# 06_MOV16_SourceRegister.net
KiCad netlist of a schematic drawn in EAGLE
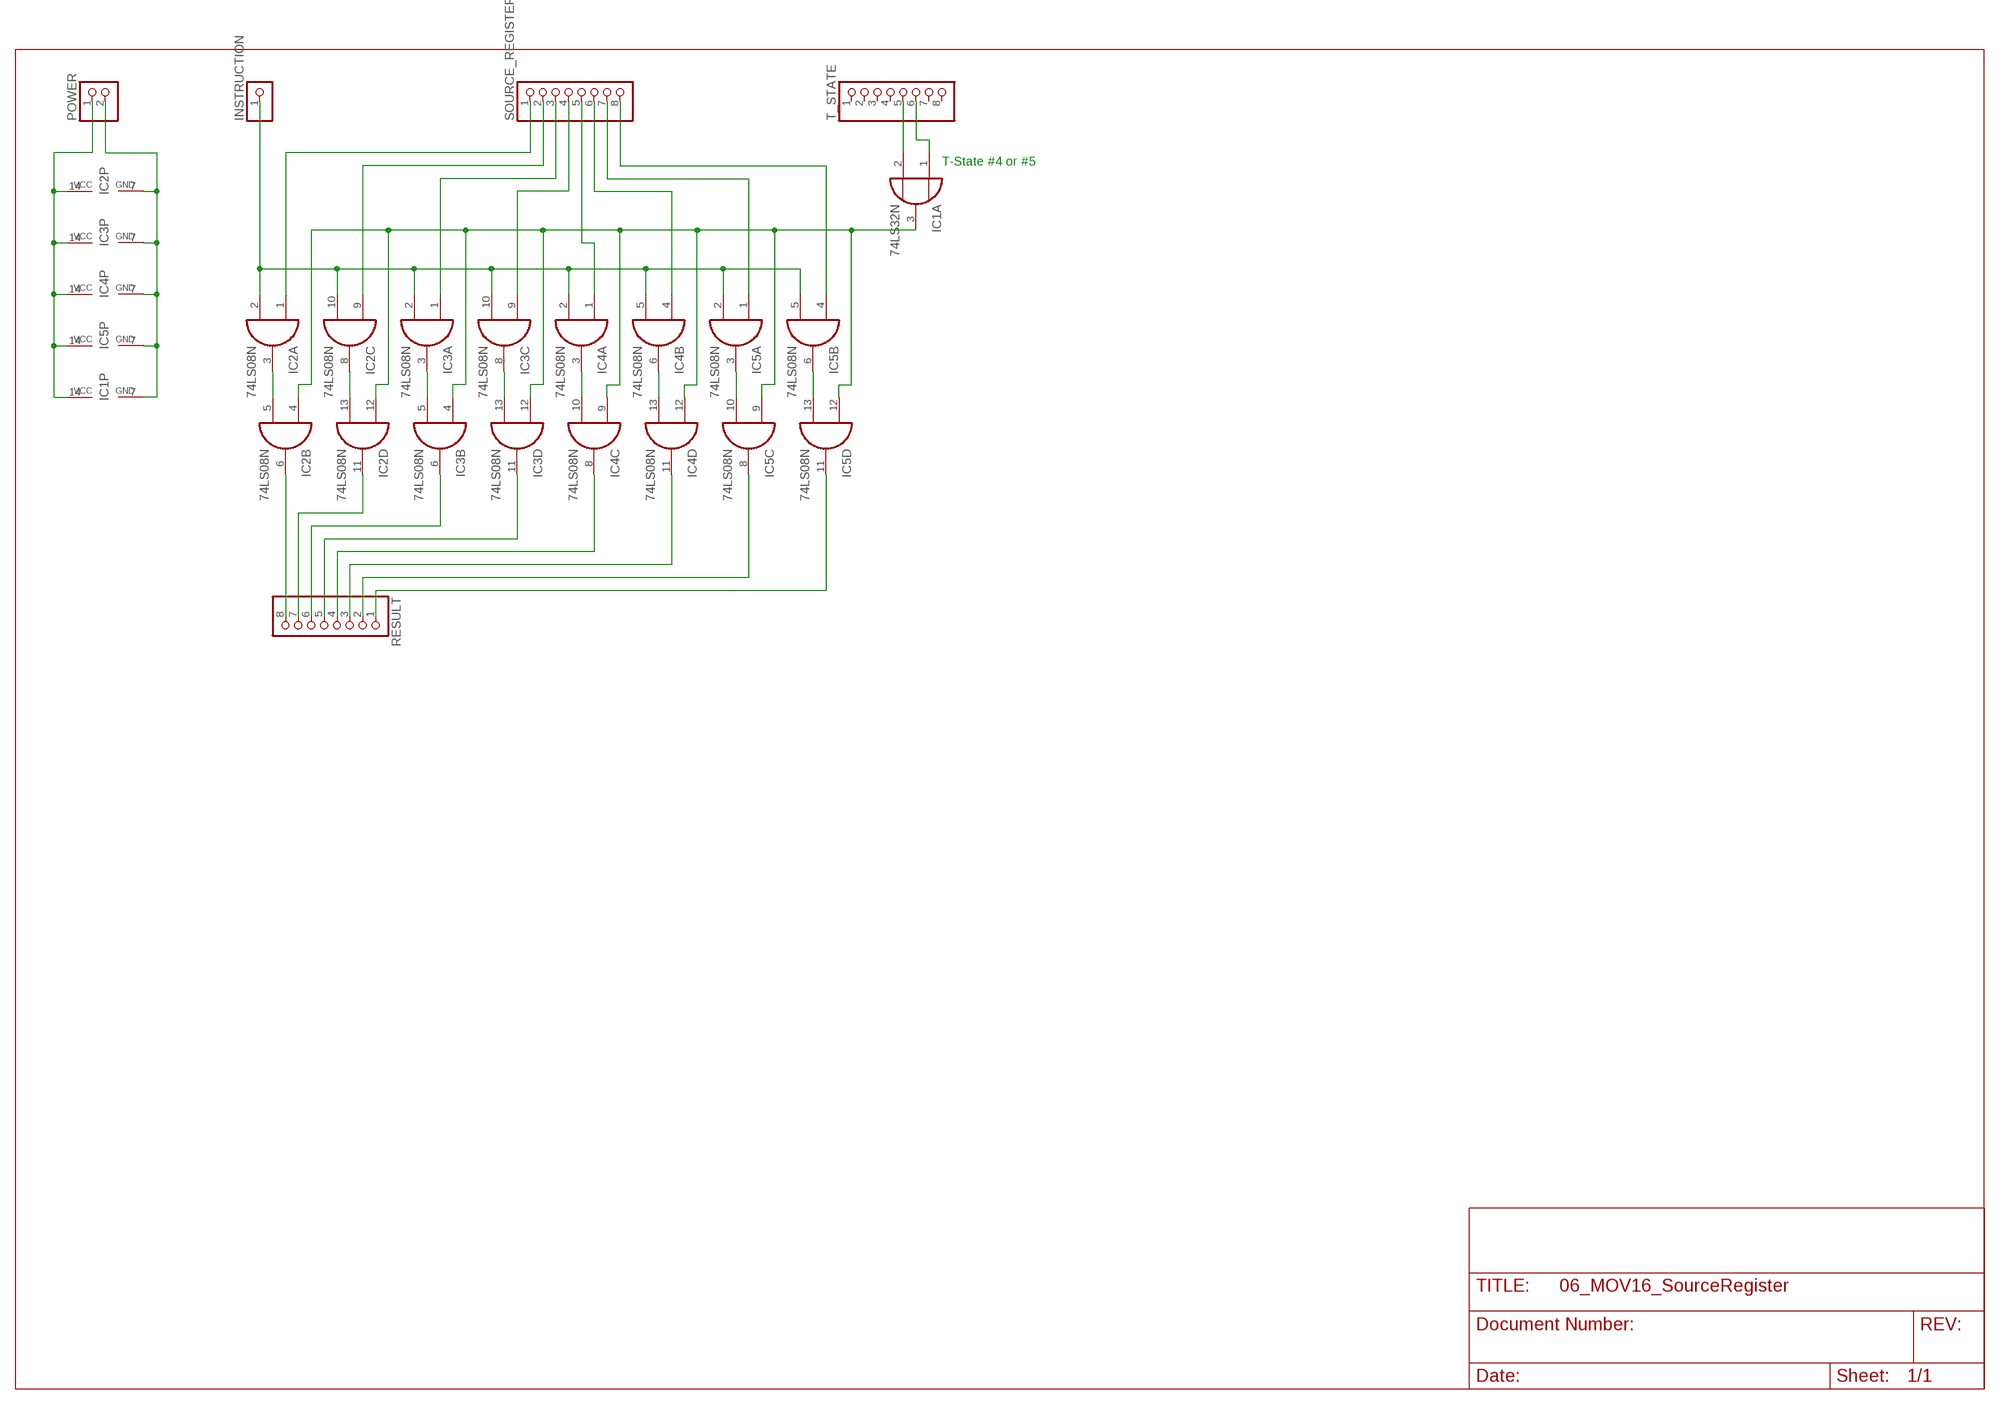
[diagram p0: schematic, sheet 1]

(export (version "E")
  (design (tool "Eeschema 10.0.6"))
  (components
    (comp (ref "IC1")
      (value "74LS32N")
      (footprint "eagle-import:DIL14")
      (libsource (lib "eagle-import") (part "7432NLS"))
    )
    (comp (ref "IC2")
      (value "74LS08N")
      (footprint "eagle-import:DIL14")
      (libsource (lib "eagle-import") (part "7408NLS"))
    )
    (comp (ref "IC3")
      (value "74LS08N")
      (footprint "eagle-import:DIL14")
      (libsource (lib "eagle-import") (part "7408NLS"))
    )
    (comp (ref "IC4")
      (value "74LS08N")
      (footprint "eagle-import:DIL14")
      (libsource (lib "eagle-import") (part "7408NLS"))
    )
    (comp (ref "IC5")
      (value "74LS08N")
      (footprint "eagle-import:DIL14")
      (libsource (lib "eagle-import") (part "7408NLS"))
    )
    (comp (ref "INSTRUCTION")
      (value "PINHD-1X1")
      (footprint "eagle-import:1X01")
      (libsource (lib "eagle-import") (part "PINHD-1X1"))
    )
    (comp (ref "POWER")
      (value "PINHD-1X2")
      (footprint "eagle-import:1X02")
      (libsource (lib "eagle-import") (part "PINHD-1X2"))
    )
    (comp (ref "RESULT")
      (value "PINHD-1X8")
      (footprint "eagle-import:1X08")
      (libsource (lib "eagle-import") (part "PINHD-1X8"))
    )
    (comp (ref "SOURCE_REGISTER")
      (value "PINHD-1X8")
      (footprint "eagle-import:1X08")
      (libsource (lib "eagle-import") (part "PINHD-1X8"))
    )
    (comp (ref "T_STATE")
      (value "PINHD-1X8")
      (footprint "eagle-import:1X08")
      (libsource (lib "eagle-import") (part "PINHD-1X8"))
    )
  )
  (nets
    (net (code "1") (name "Net-(IC1A-I0)") (class "Default")
      (node (ref "IC1") (pin "1") (pinfunction "I0_1") (pintype "input"))
      (node (ref "T_STATE") (pin "6") (pinfunction "6_6") (pintype "passive"))
    )
    (net (code "2") (name "Net-(IC1A-I1)") (class "Default")
      (node (ref "IC1") (pin "2") (pinfunction "I1_2") (pintype "input"))
      (node (ref "T_STATE") (pin "5") (pinfunction "5_5") (pintype "passive"))
    )
    (net (code "3") (name "Net-(IC1A-O)") (class "Default")
      (node (ref "IC1") (pin "3") (pinfunction "O_3") (pintype "output"))
      (node (ref "IC2") (pin "12") (pinfunction "I0_12") (pintype "input"))
      (node (ref "IC2") (pin "4") (pinfunction "I0_4") (pintype "input"))
      (node (ref "IC3") (pin "12") (pinfunction "I0_12") (pintype "input"))
      (node (ref "IC3") (pin "4") (pinfunction "I0_4") (pintype "input"))
      (node (ref "IC4") (pin "12") (pinfunction "I0_12") (pintype "input"))
      (node (ref "IC4") (pin "9") (pinfunction "I0_9") (pintype "input"))
      (node (ref "IC5") (pin "12") (pinfunction "I0_12") (pintype "input"))
      (node (ref "IC5") (pin "9") (pinfunction "I0_9") (pintype "input"))
    )
    (net (code "4") (name "Net-(IC1E-GND)") (class "Default")
      (node (ref "IC1") (pin "7") (pinfunction "GND_7") (pintype "power_in"))
      (node (ref "IC2") (pin "7") (pinfunction "GND_7") (pintype "power_in"))
      (node (ref "IC3") (pin "7") (pinfunction "GND_7") (pintype "power_in"))
      (node (ref "IC4") (pin "7") (pinfunction "GND_7") (pintype "power_in"))
      (node (ref "IC5") (pin "7") (pinfunction "GND_7") (pintype "power_in"))
      (node (ref "POWER") (pin "2") (pinfunction "2_2") (pintype "passive"))
    )
    (net (code "5") (name "Net-(IC1E-VCC)") (class "Default")
      (node (ref "IC1") (pin "14") (pinfunction "VCC_14") (pintype "power_in"))
      (node (ref "IC2") (pin "14") (pinfunction "VCC_14") (pintype "power_in"))
      (node (ref "IC3") (pin "14") (pinfunction "VCC_14") (pintype "power_in"))
      (node (ref "IC4") (pin "14") (pinfunction "VCC_14") (pintype "power_in"))
      (node (ref "IC5") (pin "14") (pinfunction "VCC_14") (pintype "power_in"))
      (node (ref "POWER") (pin "1") (pinfunction "1_1") (pintype "passive"))
    )
    (net (code "6") (name "Net-(IC2A-I0)") (class "Default")
      (node (ref "IC2") (pin "1") (pinfunction "I0_1") (pintype "input"))
      (node (ref "SOURCE_REGISTER") (pin "1") (pinfunction "1_1") (pintype "passive"))
    )
    (net (code "7") (name "Net-(IC2A-I1)") (class "Default")
      (node (ref "IC2") (pin "10") (pinfunction "I1_10") (pintype "input"))
      (node (ref "IC2") (pin "2") (pinfunction "I1_2") (pintype "input"))
      (node (ref "IC3") (pin "10") (pinfunction "I1_10") (pintype "input"))
      (node (ref "IC3") (pin "2") (pinfunction "I1_2") (pintype "input"))
      (node (ref "IC4") (pin "2") (pinfunction "I1_2") (pintype "input"))
      (node (ref "IC4") (pin "5") (pinfunction "I1_5") (pintype "input"))
      (node (ref "IC5") (pin "2") (pinfunction "I1_2") (pintype "input"))
      (node (ref "IC5") (pin "5") (pinfunction "I1_5") (pintype "input"))
      (node (ref "INSTRUCTION") (pin "1") (pinfunction "1_1") (pintype "passive"))
    )
    (net (code "8") (name "Net-(IC2A-O)") (class "Default")
      (node (ref "IC2") (pin "3") (pinfunction "O_3") (pintype "output"))
      (node (ref "IC2") (pin "5") (pinfunction "I1_5") (pintype "input"))
    )
    (net (code "9") (name "Net-(IC2B-O)") (class "Default")
      (node (ref "IC2") (pin "6") (pinfunction "O_6") (pintype "output"))
      (node (ref "RESULT") (pin "8") (pinfunction "8_8") (pintype "passive"))
    )
    (net (code "10") (name "Net-(IC2C-I0)") (class "Default")
      (node (ref "IC2") (pin "9") (pinfunction "I0_9") (pintype "input"))
      (node (ref "SOURCE_REGISTER") (pin "2") (pinfunction "2_2") (pintype "passive"))
    )
    (net (code "11") (name "Net-(IC2C-O)") (class "Default")
      (node (ref "IC2") (pin "13") (pinfunction "I1_13") (pintype "input"))
      (node (ref "IC2") (pin "8") (pinfunction "O_8") (pintype "output"))
    )
    (net (code "12") (name "Net-(IC2D-O)") (class "Default")
      (node (ref "IC2") (pin "11") (pinfunction "O_11") (pintype "output"))
      (node (ref "RESULT") (pin "7") (pinfunction "7_7") (pintype "passive"))
    )
    (net (code "13") (name "Net-(IC3A-I0)") (class "Default")
      (node (ref "IC3") (pin "1") (pinfunction "I0_1") (pintype "input"))
      (node (ref "SOURCE_REGISTER") (pin "3") (pinfunction "3_3") (pintype "passive"))
    )
    (net (code "14") (name "Net-(IC3A-O)") (class "Default")
      (node (ref "IC3") (pin "3") (pinfunction "O_3") (pintype "output"))
      (node (ref "IC3") (pin "5") (pinfunction "I1_5") (pintype "input"))
    )
    (net (code "15") (name "Net-(IC3B-O)") (class "Default")
      (node (ref "IC3") (pin "6") (pinfunction "O_6") (pintype "output"))
      (node (ref "RESULT") (pin "6") (pinfunction "6_6") (pintype "passive"))
    )
    (net (code "16") (name "Net-(IC3C-I0)") (class "Default")
      (node (ref "IC3") (pin "9") (pinfunction "I0_9") (pintype "input"))
      (node (ref "SOURCE_REGISTER") (pin "4") (pinfunction "4_4") (pintype "passive"))
    )
    (net (code "17") (name "Net-(IC3C-O)") (class "Default")
      (node (ref "IC3") (pin "13") (pinfunction "I1_13") (pintype "input"))
      (node (ref "IC3") (pin "8") (pinfunction "O_8") (pintype "output"))
    )
    (net (code "18") (name "Net-(IC3D-O)") (class "Default")
      (node (ref "IC3") (pin "11") (pinfunction "O_11") (pintype "output"))
      (node (ref "RESULT") (pin "5") (pinfunction "5_5") (pintype "passive"))
    )
    (net (code "19") (name "Net-(IC4A-I0)") (class "Default")
      (node (ref "IC4") (pin "1") (pinfunction "I0_1") (pintype "input"))
      (node (ref "SOURCE_REGISTER") (pin "5") (pinfunction "5_5") (pintype "passive"))
    )
    (net (code "20") (name "Net-(IC4A-O)") (class "Default")
      (node (ref "IC4") (pin "10") (pinfunction "I1_10") (pintype "input"))
      (node (ref "IC4") (pin "3") (pinfunction "O_3") (pintype "output"))
    )
    (net (code "21") (name "Net-(IC4B-I0)") (class "Default")
      (node (ref "IC4") (pin "4") (pinfunction "I0_4") (pintype "input"))
      (node (ref "SOURCE_REGISTER") (pin "6") (pinfunction "6_6") (pintype "passive"))
    )
    (net (code "22") (name "Net-(IC4B-O)") (class "Default")
      (node (ref "IC4") (pin "13") (pinfunction "I1_13") (pintype "input"))
      (node (ref "IC4") (pin "6") (pinfunction "O_6") (pintype "output"))
    )
    (net (code "23") (name "Net-(IC4C-O)") (class "Default")
      (node (ref "IC4") (pin "8") (pinfunction "O_8") (pintype "output"))
      (node (ref "RESULT") (pin "4") (pinfunction "4_4") (pintype "passive"))
    )
    (net (code "24") (name "Net-(IC4D-O)") (class "Default")
      (node (ref "IC4") (pin "11") (pinfunction "O_11") (pintype "output"))
      (node (ref "RESULT") (pin "3") (pinfunction "3_3") (pintype "passive"))
    )
    (net (code "25") (name "Net-(IC5A-I0)") (class "Default")
      (node (ref "IC5") (pin "1") (pinfunction "I0_1") (pintype "input"))
      (node (ref "SOURCE_REGISTER") (pin "7") (pinfunction "7_7") (pintype "passive"))
    )
    (net (code "26") (name "Net-(IC5A-O)") (class "Default")
      (node (ref "IC5") (pin "10") (pinfunction "I1_10") (pintype "input"))
      (node (ref "IC5") (pin "3") (pinfunction "O_3") (pintype "output"))
    )
    (net (code "27") (name "Net-(IC5B-I0)") (class "Default")
      (node (ref "IC5") (pin "4") (pinfunction "I0_4") (pintype "input"))
      (node (ref "SOURCE_REGISTER") (pin "8") (pinfunction "8_8") (pintype "passive"))
    )
    (net (code "28") (name "Net-(IC5B-O)") (class "Default")
      (node (ref "IC5") (pin "13") (pinfunction "I1_13") (pintype "input"))
      (node (ref "IC5") (pin "6") (pinfunction "O_6") (pintype "output"))
    )
    (net (code "29") (name "Net-(IC5C-O)") (class "Default")
      (node (ref "IC5") (pin "8") (pinfunction "O_8") (pintype "output"))
      (node (ref "RESULT") (pin "2") (pinfunction "2_2") (pintype "passive"))
    )
    (net (code "30") (name "Net-(IC5D-O)") (class "Default")
      (node (ref "IC5") (pin "11") (pinfunction "O_11") (pintype "output"))
      (node (ref "RESULT") (pin "1") (pinfunction "1_1") (pintype "passive"))
    )
    (net (code "31") (name "unconnected-(T_STATE-Pad1)") (class "Default")
      (node (ref "T_STATE") (pin "1") (pinfunction "1_1") (pintype "passive"))
    )
    (net (code "32") (name "unconnected-(T_STATE-Pad2)") (class "Default")
      (node (ref "T_STATE") (pin "2") (pinfunction "2_2") (pintype "passive"))
    )
    (net (code "33") (name "unconnected-(T_STATE-Pad3)") (class "Default")
      (node (ref "T_STATE") (pin "3") (pinfunction "3_3") (pintype "passive"))
    )
    (net (code "34") (name "unconnected-(T_STATE-Pad4)") (class "Default")
      (node (ref "T_STATE") (pin "4") (pinfunction "4_4") (pintype "passive"))
    )
    (net (code "35") (name "unconnected-(T_STATE-Pad7)") (class "Default")
      (node (ref "T_STATE") (pin "7") (pinfunction "7_7") (pintype "passive"))
    )
    (net (code "36") (name "unconnected-(T_STATE-Pad8)") (class "Default")
      (node (ref "T_STATE") (pin "8") (pinfunction "8_8") (pintype "passive"))
    )
  )
)
